# Connection_SCH.net
KiCad netlist of a schematic drawn in Altium Designer
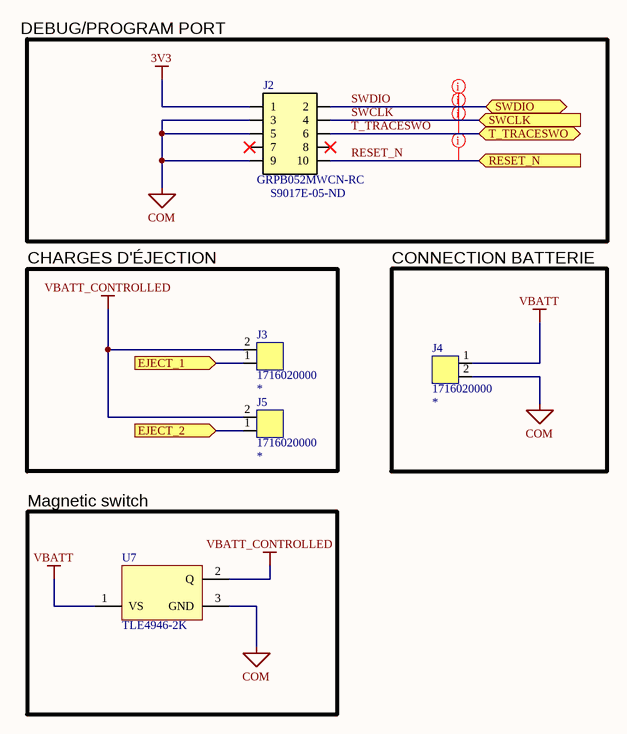
[diagram p0: Connection_SCH.SchDoc]

(export (version "E")
  (design (tool "Eeschema 10.0.6"))
  (components
    (comp (ref "J2")
      (value "GRPB052MWCN-RC")
      (footprint "HEADER 50MIL 10POS MALE")
      (description "CONN HEADER R/A 10POS 1.27MM")
      (fields (field (name "SUPPLIER PART NUMBER 1") "S9017E-05-ND"))
      (libsource (lib "Rockets_CONN") (part "GRPB052MWCN-RC"))
    )
    (comp (ref "J3")
      (value "1716020000")
      (footprint "1716020000")
      (description "CONN TERM BLOCK PCB 5.08MM 2POS")
      (fields (field (name "VOLTAGE") "300V") (field (name "NAME") "*"))
      (libsource (lib "Rockets_CONN") (part "1716020000"))
    )
    (comp (ref "J4")
      (value "1716020000")
      (footprint "1716020000")
      (description "CONN TERM BLOCK PCB 5.08MM 2POS")
      (fields (field (name "VOLTAGE") "300V") (field (name "NAME") "*"))
      (libsource (lib "") (part "1716020000_1"))
    )
    (comp (ref "J5")
      (value "1716020000")
      (footprint "1716020000")
      (description "CONN TERM BLOCK PCB 5.08MM 2POS")
      (fields (field (name "VOLTAGE") "300V") (field (name "NAME") "*"))
      (libsource (lib "Rockets_CONN") (part "1716020000"))
    )
    (comp (ref "U7")
      (value "TLE4946-2K")
      (footprint "INF-PG-SC59_M")
      (description "High Precision Hall Effect Latch, PG-SC59, Reel, Green")
      (fields (field (name "MANUFACTURER") "Infineon"))
      (libsource (lib "Altium Content Vault") (part "INF-TLE49XX-SC59-3"))
    )
  )
  (nets
    (net (code "1") (name "/EJECT_1") (class "Default")
      (node (ref "J3") (pin "1") (pinfunction "1_1") (pintype "passive"))
    )
    (net (code "2") (name "/EJECT_2") (class "Default")
      (node (ref "J5") (pin "1") (pinfunction "1_1") (pintype "passive"))
    )
    (net (code "3") (name "/RESET_N") (class "Default")
      (node (ref "J2") (pin "10") (pinfunction "10_10") (pintype "passive"))
    )
    (net (code "4") (name "/SWCLK") (class "Default")
      (node (ref "J2") (pin "4") (pinfunction "4_4") (pintype "passive"))
    )
    (net (code "5") (name "/SWDIO") (class "Default")
      (node (ref "J2") (pin "2") (pinfunction "2_2") (pintype "passive"))
    )
    (net (code "6") (name "/T_TRACESWO") (class "Default")
      (node (ref "J2") (pin "6") (pinfunction "6_6") (pintype "passive"))
    )
    (net (code "7") (name "3V3") (class "Default")
      (node (ref "J2") (pin "1") (pinfunction "1_1") (pintype "passive"))
    )
    (net (code "8") (name "COM") (class "Default")
      (node (ref "J2") (pin "3") (pinfunction "3_3") (pintype "passive"))
      (node (ref "J2") (pin "5") (pinfunction "5_5") (pintype "passive"))
      (node (ref "J2") (pin "9") (pinfunction "9_9") (pintype "passive"))
      (node (ref "J4") (pin "2") (pinfunction "2_2") (pintype "passive"))
      (node (ref "U7") (pin "3") (pinfunction "GND_3") (pintype "power_in"))
    )
    (net (code "9") (name "VBATT") (class "Default")
      (node (ref "J4") (pin "1") (pinfunction "1_1") (pintype "passive"))
      (node (ref "U7") (pin "1") (pinfunction "VS_1") (pintype "power_in"))
    )
    (net (code "10") (name "VBATT_CONTROLLED") (class "Default")
      (node (ref "J3") (pin "2") (pinfunction "2_2") (pintype "passive"))
      (node (ref "J5") (pin "2") (pinfunction "2_2") (pintype "passive"))
      (node (ref "U7") (pin "2") (pinfunction "Q_2") (pintype "open_collector"))
    )
    (net (code "11") (name "unconnected-(J2-Pad7)") (class "Default")
      (node (ref "J2") (pin "7") (pinfunction "7_7") (pintype "passive+no_connect"))
    )
    (net (code "12") (name "unconnected-(J2-Pad8)") (class "Default")
      (node (ref "J2") (pin "8") (pinfunction "8_8") (pintype "passive+no_connect"))
    )
  )
)
